# DASHBOARD.net
KiCad netlist of a schematic drawn in Altium Designer
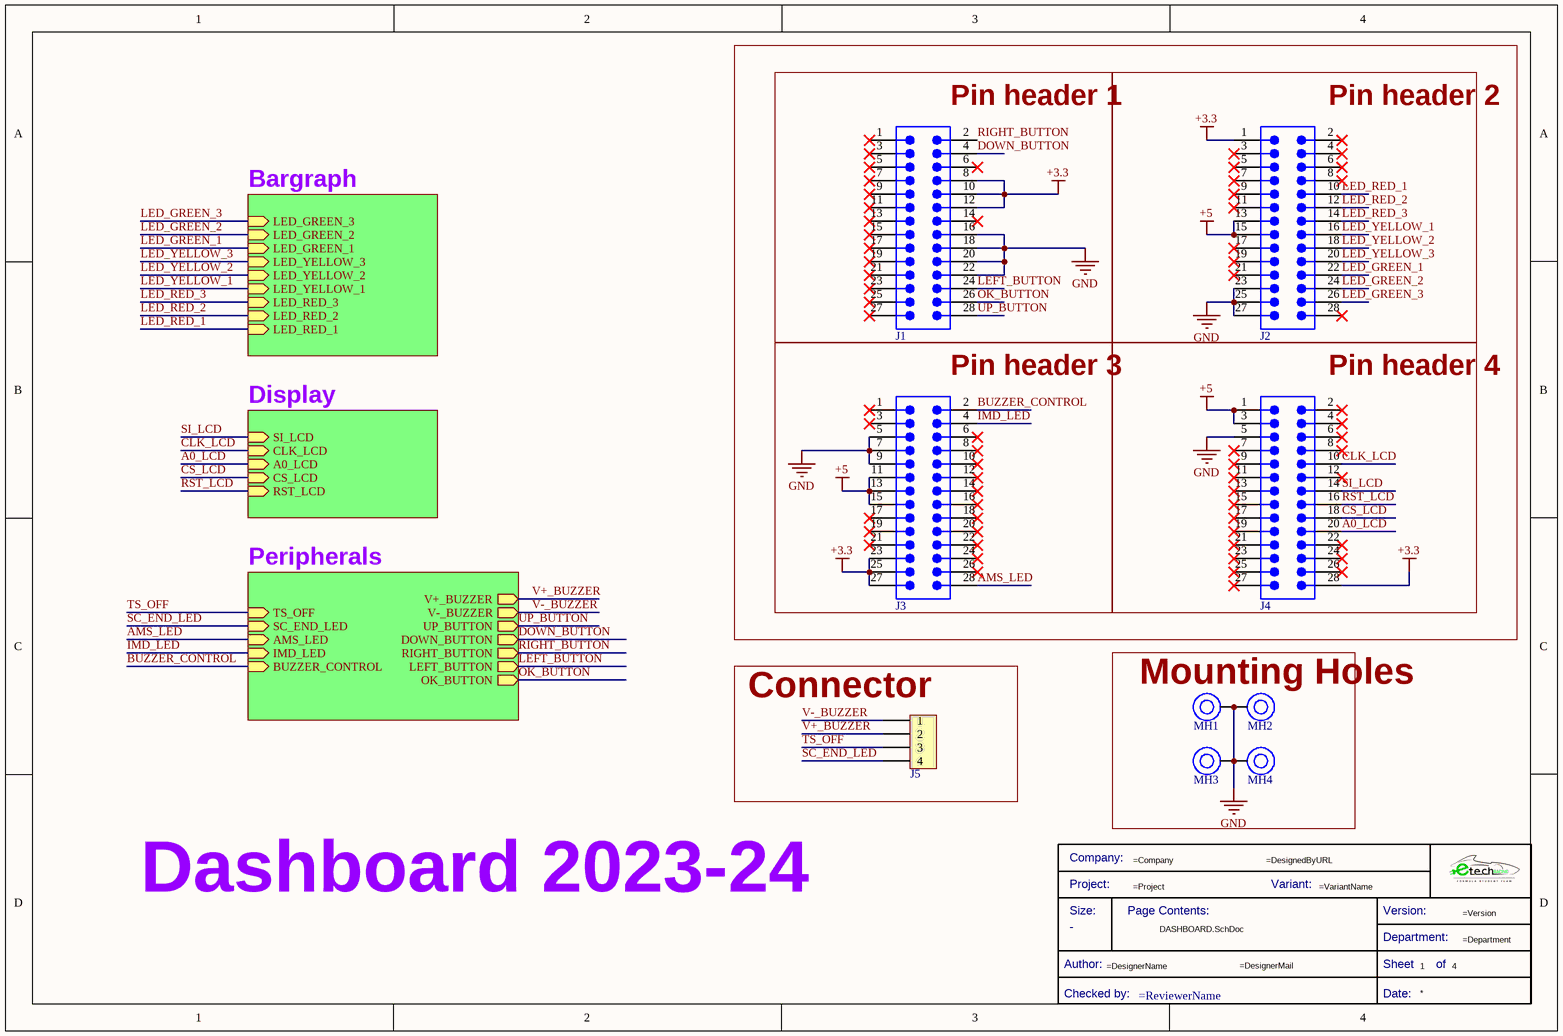
[diagram p0: DASHBOARD.SchDoc]

(export (version "E")
  (design (tool "Eeschema 10.0.6"))
  (components
    (comp (ref "J1")
      (value "62132821021")
      (footprint "62132821021")
      (description "WR-PHD Pin Header, SMT, Vertical, pitch 1.27mm, 2 Row, 28P")
      (fields (field (name "MANUFACTURER") "Wurth Elektronik"))
      (libsource (lib "Electromechanical") (part "62132821021"))
    )
    (comp (ref "J2")
      (value "62132821021")
      (footprint "62132821021")
      (description "WR-PHD Pin Header, SMT, Vertical, pitch 1.27mm, 2 Row, 28P")
      (fields (field (name "MANUFACTURER") "Wurth Elektronik"))
      (libsource (lib "Electromechanical") (part "62132821021"))
    )
    (comp (ref "J3")
      (value "62132821021")
      (footprint "62132821021")
      (description "WR-PHD Pin Header, SMT, Vertical, pitch 1.27mm, 2 Row, 28P")
      (fields (field (name "MANUFACTURER") "Wurth Elektronik"))
      (libsource (lib "Electromechanical") (part "62132821021"))
    )
    (comp (ref "J4")
      (value "62132821021")
      (footprint "62132821021")
      (description "WR-PHD Pin Header, SMT, Vertical, pitch 1.27mm, 2 Row, 28P")
      (fields (field (name "MANUFACTURER") "Wurth Elektronik"))
      (libsource (lib "Electromechanical") (part "62132821021"))
    )
    (comp (ref "J5")
      (value "436500400")
      (footprint "J_MicroFit_1x4")
      (description "Connector Wire to Board Header 4 Position 3mm Solder Right Angle Thru-Hole Tray")
      (libsource (lib "Electromechanical") (part "J_MicroFit_1x4"))
    )
    (comp (ref "MH1")
      (value "Mounting_Hole_M3")
      (footprint "Mounting_Hole_M3")
      (libsource (lib "Electromechanical") (part "Mounting_Hole_M3"))
    )
    (comp (ref "MH2")
      (value "Mounting_Hole_M3")
      (footprint "Mounting_Hole_M3")
      (libsource (lib "Electromechanical") (part "Mounting_Hole_M3"))
    )
    (comp (ref "MH3")
      (value "Mounting_Hole_M3")
      (footprint "Mounting_Hole_M3")
      (libsource (lib "Electromechanical") (part "Mounting_Hole_M3"))
    )
    (comp (ref "MH4")
      (value "Mounting_Hole_M3")
      (footprint "Mounting_Hole_M3")
      (libsource (lib "Electromechanical") (part "Mounting_Hole_M3"))
    )
  )
  (nets
    (net (code "1") (name "+3.3") (class "Default")
      (node (ref "J1") (pin "10") (pinfunction "10_10") (pintype "passive"))
      (node (ref "J1") (pin "12") (pinfunction "12_12") (pintype "passive"))
      (node (ref "J1") (pin "8") (pinfunction "8_8") (pintype "passive"))
      (node (ref "J2") (pin "1") (pinfunction "1_1") (pintype "passive"))
      (node (ref "J3") (pin "23") (pinfunction "23_23") (pintype "passive"))
      (node (ref "J3") (pin "25") (pinfunction "25_25") (pintype "passive"))
      (node (ref "J3") (pin "27") (pinfunction "27_27") (pintype "passive"))
      (node (ref "J4") (pin "28") (pinfunction "28_28") (pintype "passive"))
    )
    (net (code "2") (name "+5") (class "Default")
      (node (ref "J2") (pin "13") (pinfunction "13_13") (pintype "passive"))
      (node (ref "J2") (pin "15") (pinfunction "15_15") (pintype "passive"))
      (node (ref "J3") (pin "11") (pinfunction "11_11") (pintype "passive"))
      (node (ref "J3") (pin "13") (pinfunction "13_13") (pintype "passive"))
      (node (ref "J3") (pin "15") (pinfunction "15_15") (pintype "passive"))
      (node (ref "J4") (pin "1") (pinfunction "1_1") (pintype "passive"))
      (node (ref "J4") (pin "3") (pinfunction "3_3") (pintype "passive"))
    )
    (net (code "4") (name "/A0_LCD") (class "Default")
      (node (ref "J4") (pin "20") (pinfunction "20_20") (pintype "passive"))
    )
    (net (code "5") (name "/AMS_LED") (class "Default")
      (node (ref "J3") (pin "28") (pinfunction "28_28") (pintype "passive"))
    )
    (net (code "6") (name "/BUZZER_CONTROL") (class "Default")
      (node (ref "J3") (pin "2") (pinfunction "2_2") (pintype "passive"))
    )
    (net (code "7") (name "/CLK_LCD") (class "Default")
      (node (ref "J4") (pin "10") (pinfunction "10_10") (pintype "passive"))
    )
    (net (code "8") (name "/CS_LCD") (class "Default")
      (node (ref "J4") (pin "18") (pinfunction "18_18") (pintype "passive"))
    )
    (net (code "9") (name "/DOWN_BUTTON") (class "Default")
      (node (ref "J1") (pin "4") (pinfunction "4_4") (pintype "passive"))
    )
    (net (code "10") (name "/IMD_LED") (class "Default")
      (node (ref "J3") (pin "4") (pinfunction "4_4") (pintype "passive"))
    )
    (net (code "11") (name "/LED_GREEN_1") (class "Default")
      (node (ref "J2") (pin "22") (pinfunction "22_22") (pintype "passive"))
    )
    (net (code "12") (name "/LED_GREEN_2") (class "Default")
      (node (ref "J2") (pin "24") (pinfunction "24_24") (pintype "passive"))
    )
    (net (code "13") (name "/LED_GREEN_3") (class "Default")
      (node (ref "J2") (pin "26") (pinfunction "26_26") (pintype "passive"))
    )
    (net (code "14") (name "/LED_RED_1") (class "Default")
      (node (ref "J2") (pin "10") (pinfunction "10_10") (pintype "passive"))
    )
    (net (code "15") (name "/LED_RED_2") (class "Default")
      (node (ref "J2") (pin "12") (pinfunction "12_12") (pintype "passive"))
    )
    (net (code "16") (name "/LED_RED_3") (class "Default")
      (node (ref "J2") (pin "14") (pinfunction "14_14") (pintype "passive"))
    )
    (net (code "17") (name "/LED_YELLOW_1") (class "Default")
      (node (ref "J2") (pin "16") (pinfunction "16_16") (pintype "passive"))
    )
    (net (code "18") (name "/LED_YELLOW_2") (class "Default")
      (node (ref "J2") (pin "18") (pinfunction "18_18") (pintype "passive"))
    )
    (net (code "19") (name "/LED_YELLOW_3") (class "Default")
      (node (ref "J2") (pin "20") (pinfunction "20_20") (pintype "passive"))
    )
    (net (code "20") (name "/LEFT_BUTTON") (class "Default")
      (node (ref "J1") (pin "24") (pinfunction "24_24") (pintype "passive"))
    )
    (net (code "21") (name "/OK_BUTTON") (class "Default")
      (node (ref "J1") (pin "26") (pinfunction "26_26") (pintype "passive"))
    )
    (net (code "22") (name "/RIGHT_BUTTON") (class "Default")
      (node (ref "J1") (pin "2") (pinfunction "2_2") (pintype "passive"))
    )
    (net (code "23") (name "/RST_LCD") (class "Default")
      (node (ref "J4") (pin "16") (pinfunction "16_16") (pintype "passive"))
    )
    (net (code "24") (name "/SC_END_LED") (class "Default")
      (node (ref "J5") (pin "4") (pinfunction "4_4") (pintype "passive"))
    )
    (net (code "25") (name "/SI_LCD") (class "Default")
      (node (ref "J4") (pin "14") (pinfunction "14_14") (pintype "passive"))
    )
    (net (code "26") (name "/TS_OFF") (class "Default")
      (node (ref "J5") (pin "3") (pinfunction "3_3") (pintype "passive"))
    )
    (net (code "27") (name "/UP_BUTTON") (class "Default")
      (node (ref "J1") (pin "28") (pinfunction "28_28") (pintype "passive"))
    )
    (net (code "28") (name "/V+_BUZZER") (class "Default")
      (node (ref "J5") (pin "2") (pinfunction "2_2") (pintype "passive"))
    )
    (net (code "29") (name "/V-_BUZZER") (class "Default")
      (node (ref "J5") (pin "1") (pinfunction "1_1") (pintype "passive"))
    )
    (net (code "30") (name "GND") (class "Default")
      (node (ref "J1") (pin "16") (pinfunction "16_16") (pintype "passive"))
      (node (ref "J1") (pin "18") (pinfunction "18_18") (pintype "passive"))
      (node (ref "J1") (pin "20") (pinfunction "20_20") (pintype "passive"))
      (node (ref "J1") (pin "22") (pinfunction "22_22") (pintype "passive"))
      (node (ref "J2") (pin "23") (pinfunction "23_23") (pintype "passive"))
      (node (ref "J2") (pin "25") (pinfunction "25_25") (pintype "passive"))
      (node (ref "J2") (pin "27") (pinfunction "27_27") (pintype "passive"))
      (node (ref "J3") (pin "5") (pinfunction "5_5") (pintype "passive"))
      (node (ref "J3") (pin "7") (pinfunction "7_7") (pintype "passive"))
      (node (ref "J3") (pin "9") (pinfunction "9_9") (pintype "passive"))
      (node (ref "J4") (pin "5") (pinfunction "5_5") (pintype "passive"))
      (node (ref "MH1") (pin "1") (pinfunction "1_1") (pintype "passive"))
      (node (ref "MH2") (pin "1") (pinfunction "1_1") (pintype "passive"))
      (node (ref "MH3") (pin "1") (pinfunction "1_1") (pintype "passive"))
      (node (ref "MH4") (pin "1") (pinfunction "1_1") (pintype "passive"))
    )
    (net (code "31") (name "unconnected-(J1-Pad1)") (class "Default")
      (node (ref "J1") (pin "1") (pinfunction "1_1") (pintype "passive+no_connect"))
    )
    (net (code "32") (name "unconnected-(J1-Pad3)") (class "Default")
      (node (ref "J1") (pin "3") (pinfunction "3_3") (pintype "passive+no_connect"))
    )
    (net (code "33") (name "unconnected-(J1-Pad5)") (class "Default")
      (node (ref "J1") (pin "5") (pinfunction "5_5") (pintype "passive+no_connect"))
    )
    (net (code "34") (name "unconnected-(J1-Pad6)") (class "Default")
      (node (ref "J1") (pin "6") (pinfunction "6_6") (pintype "passive+no_connect"))
    )
    (net (code "35") (name "unconnected-(J1-Pad7)") (class "Default")
      (node (ref "J1") (pin "7") (pinfunction "7_7") (pintype "passive+no_connect"))
    )
    (net (code "36") (name "unconnected-(J1-Pad9)") (class "Default")
      (node (ref "J1") (pin "9") (pinfunction "9_9") (pintype "passive+no_connect"))
    )
    (net (code "37") (name "unconnected-(J1-Pad11)") (class "Default")
      (node (ref "J1") (pin "11") (pinfunction "11_11") (pintype "passive+no_connect"))
    )
    (net (code "38") (name "unconnected-(J1-Pad13)") (class "Default")
      (node (ref "J1") (pin "13") (pinfunction "13_13") (pintype "passive+no_connect"))
    )
    (net (code "39") (name "unconnected-(J1-Pad14)") (class "Default")
      (node (ref "J1") (pin "14") (pinfunction "14_14") (pintype "passive+no_connect"))
    )
    (net (code "40") (name "unconnected-(J1-Pad15)") (class "Default")
      (node (ref "J1") (pin "15") (pinfunction "15_15") (pintype "passive+no_connect"))
    )
    (net (code "41") (name "unconnected-(J1-Pad17)") (class "Default")
      (node (ref "J1") (pin "17") (pinfunction "17_17") (pintype "passive+no_connect"))
    )
    (net (code "42") (name "unconnected-(J1-Pad19)") (class "Default")
      (node (ref "J1") (pin "19") (pinfunction "19_19") (pintype "passive+no_connect"))
    )
    (net (code "43") (name "unconnected-(J1-Pad21)") (class "Default")
      (node (ref "J1") (pin "21") (pinfunction "21_21") (pintype "passive+no_connect"))
    )
    (net (code "44") (name "unconnected-(J1-Pad23)") (class "Default")
      (node (ref "J1") (pin "23") (pinfunction "23_23") (pintype "passive+no_connect"))
    )
    (net (code "45") (name "unconnected-(J1-Pad25)") (class "Default")
      (node (ref "J1") (pin "25") (pinfunction "25_25") (pintype "passive+no_connect"))
    )
    (net (code "46") (name "unconnected-(J1-Pad27)") (class "Default")
      (node (ref "J1") (pin "27") (pinfunction "27_27") (pintype "passive+no_connect"))
    )
    (net (code "47") (name "unconnected-(J2-Pad2)") (class "Default")
      (node (ref "J2") (pin "2") (pinfunction "2_2") (pintype "passive+no_connect"))
    )
    (net (code "48") (name "unconnected-(J2-Pad3)") (class "Default")
      (node (ref "J2") (pin "3") (pinfunction "3_3") (pintype "passive+no_connect"))
    )
    (net (code "49") (name "unconnected-(J2-Pad4)") (class "Default")
      (node (ref "J2") (pin "4") (pinfunction "4_4") (pintype "passive+no_connect"))
    )
    (net (code "50") (name "unconnected-(J2-Pad5)") (class "Default")
      (node (ref "J2") (pin "5") (pinfunction "5_5") (pintype "passive+no_connect"))
    )
    (net (code "51") (name "unconnected-(J2-Pad6)") (class "Default")
      (node (ref "J2") (pin "6") (pinfunction "6_6") (pintype "passive+no_connect"))
    )
    (net (code "52") (name "unconnected-(J2-Pad7)") (class "Default")
      (node (ref "J2") (pin "7") (pinfunction "7_7") (pintype "passive+no_connect"))
    )
    (net (code "53") (name "unconnected-(J2-Pad8)") (class "Default")
      (node (ref "J2") (pin "8") (pinfunction "8_8") (pintype "passive+no_connect"))
    )
    (net (code "54") (name "unconnected-(J2-Pad9)") (class "Default")
      (node (ref "J2") (pin "9") (pinfunction "9_9") (pintype "passive+no_connect"))
    )
    (net (code "55") (name "unconnected-(J2-Pad11)") (class "Default")
      (node (ref "J2") (pin "11") (pinfunction "11_11") (pintype "passive+no_connect"))
    )
    (net (code "56") (name "unconnected-(J2-Pad17)") (class "Default")
      (node (ref "J2") (pin "17") (pinfunction "17_17") (pintype "passive+no_connect"))
    )
    (net (code "57") (name "unconnected-(J2-Pad19)") (class "Default")
      (node (ref "J2") (pin "19") (pinfunction "19_19") (pintype "passive+no_connect"))
    )
    (net (code "58") (name "unconnected-(J2-Pad21)") (class "Default")
      (node (ref "J2") (pin "21") (pinfunction "21_21") (pintype "passive+no_connect"))
    )
    (net (code "59") (name "unconnected-(J2-Pad28)") (class "Default")
      (node (ref "J2") (pin "28") (pinfunction "28_28") (pintype "passive+no_connect"))
    )
    (net (code "60") (name "unconnected-(J3-Pad1)") (class "Default")
      (node (ref "J3") (pin "1") (pinfunction "1_1") (pintype "passive+no_connect"))
    )
    (net (code "61") (name "unconnected-(J3-Pad3)") (class "Default")
      (node (ref "J3") (pin "3") (pinfunction "3_3") (pintype "passive+no_connect"))
    )
    (net (code "62") (name "unconnected-(J3-Pad6)") (class "Default")
      (node (ref "J3") (pin "6") (pinfunction "6_6") (pintype "passive+no_connect"))
    )
    (net (code "63") (name "unconnected-(J3-Pad8)") (class "Default")
      (node (ref "J3") (pin "8") (pinfunction "8_8") (pintype "passive+no_connect"))
    )
    (net (code "64") (name "unconnected-(J3-Pad10)") (class "Default")
      (node (ref "J3") (pin "10") (pinfunction "10_10") (pintype "passive+no_connect"))
    )
    (net (code "65") (name "unconnected-(J3-Pad12)") (class "Default")
      (node (ref "J3") (pin "12") (pinfunction "12_12") (pintype "passive+no_connect"))
    )
    (net (code "66") (name "unconnected-(J3-Pad14)") (class "Default")
      (node (ref "J3") (pin "14") (pinfunction "14_14") (pintype "passive+no_connect"))
    )
    (net (code "67") (name "unconnected-(J3-Pad16)") (class "Default")
      (node (ref "J3") (pin "16") (pinfunction "16_16") (pintype "passive+no_connect"))
    )
    (net (code "68") (name "unconnected-(J3-Pad17)") (class "Default")
      (node (ref "J3") (pin "17") (pinfunction "17_17") (pintype "passive+no_connect"))
    )
    (net (code "69") (name "unconnected-(J3-Pad18)") (class "Default")
      (node (ref "J3") (pin "18") (pinfunction "18_18") (pintype "passive+no_connect"))
    )
    (net (code "70") (name "unconnected-(J3-Pad19)") (class "Default")
      (node (ref "J3") (pin "19") (pinfunction "19_19") (pintype "passive+no_connect"))
    )
    (net (code "71") (name "unconnected-(J3-Pad20)") (class "Default")
      (node (ref "J3") (pin "20") (pinfunction "20_20") (pintype "passive+no_connect"))
    )
    (net (code "72") (name "unconnected-(J3-Pad21)") (class "Default")
      (node (ref "J3") (pin "21") (pinfunction "21_21") (pintype "passive+no_connect"))
    )
    (net (code "73") (name "unconnected-(J3-Pad22)") (class "Default")
      (node (ref "J3") (pin "22") (pinfunction "22_22") (pintype "passive+no_connect"))
    )
    (net (code "74") (name "unconnected-(J3-Pad24)") (class "Default")
      (node (ref "J3") (pin "24") (pinfunction "24_24") (pintype "passive+no_connect"))
    )
    (net (code "75") (name "unconnected-(J3-Pad26)") (class "Default")
      (node (ref "J3") (pin "26") (pinfunction "26_26") (pintype "passive+no_connect"))
    )
    (net (code "76") (name "unconnected-(J4-Pad2)") (class "Default")
      (node (ref "J4") (pin "2") (pinfunction "2_2") (pintype "passive+no_connect"))
    )
    (net (code "77") (name "unconnected-(J4-Pad4)") (class "Default")
      (node (ref "J4") (pin "4") (pinfunction "4_4") (pintype "passive+no_connect"))
    )
    (net (code "78") (name "unconnected-(J4-Pad6)") (class "Default")
      (node (ref "J4") (pin "6") (pinfunction "6_6") (pintype "passive+no_connect"))
    )
    (net (code "79") (name "unconnected-(J4-Pad7)") (class "Default")
      (node (ref "J4") (pin "7") (pinfunction "7_7") (pintype "passive+no_connect"))
    )
    (net (code "80") (name "unconnected-(J4-Pad8)") (class "Default")
      (node (ref "J4") (pin "8") (pinfunction "8_8") (pintype "passive+no_connect"))
    )
    (net (code "81") (name "unconnected-(J4-Pad9)") (class "Default")
      (node (ref "J4") (pin "9") (pinfunction "9_9") (pintype "passive+no_connect"))
    )
    (net (code "82") (name "unconnected-(J4-Pad11)") (class "Default")
      (node (ref "J4") (pin "11") (pinfunction "11_11") (pintype "passive+no_connect"))
    )
    (net (code "83") (name "unconnected-(J4-Pad12)") (class "Default")
      (node (ref "J4") (pin "12") (pinfunction "12_12") (pintype "passive+no_connect"))
    )
    (net (code "84") (name "unconnected-(J4-Pad13)") (class "Default")
      (node (ref "J4") (pin "13") (pinfunction "13_13") (pintype "passive+no_connect"))
    )
    (net (code "85") (name "unconnected-(J4-Pad15)") (class "Default")
      (node (ref "J4") (pin "15") (pinfunction "15_15") (pintype "passive+no_connect"))
    )
    (net (code "86") (name "unconnected-(J4-Pad17)") (class "Default")
      (node (ref "J4") (pin "17") (pinfunction "17_17") (pintype "passive+no_connect"))
    )
    (net (code "87") (name "unconnected-(J4-Pad19)") (class "Default")
      (node (ref "J4") (pin "19") (pinfunction "19_19") (pintype "passive+no_connect"))
    )
    (net (code "88") (name "unconnected-(J4-Pad21)") (class "Default")
      (node (ref "J4") (pin "21") (pinfunction "21_21") (pintype "passive+no_connect"))
    )
    (net (code "89") (name "unconnected-(J4-Pad22)") (class "Default")
      (node (ref "J4") (pin "22") (pinfunction "22_22") (pintype "passive+no_connect"))
    )
    (net (code "90") (name "unconnected-(J4-Pad23)") (class "Default")
      (node (ref "J4") (pin "23") (pinfunction "23_23") (pintype "passive+no_connect"))
    )
    (net (code "91") (name "unconnected-(J4-Pad24)") (class "Default")
      (node (ref "J4") (pin "24") (pinfunction "24_24") (pintype "passive+no_connect"))
    )
    (net (code "92") (name "unconnected-(J4-Pad25)") (class "Default")
      (node (ref "J4") (pin "25") (pinfunction "25_25") (pintype "passive+no_connect"))
    )
    (net (code "93") (name "unconnected-(J4-Pad26)") (class "Default")
      (node (ref "J4") (pin "26") (pinfunction "26_26") (pintype "passive+no_connect"))
    )
    (net (code "94") (name "unconnected-(J4-Pad27)") (class "Default")
      (node (ref "J4") (pin "27") (pinfunction "27_27") (pintype "passive+no_connect"))
    )
  )
)
